# rs485.net
KiCad netlist of a schematic drawn in Altium Designer
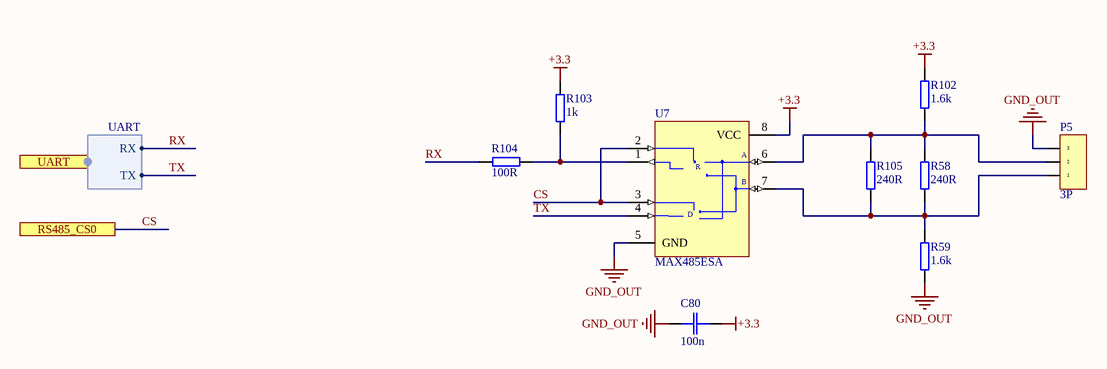
[diagram p0: rs485.SchDoc]

(export (version "E")
  (design (tool "Eeschema 10.0.6"))
  (components
    (comp (ref "C80") (value "100n") (footprint "CAP: 0603") (libsource (lib "PASSIVE") (part "C_SMD")))
    (comp (ref "P5") (value "3P") (footprint "CON: 3P V 3.5mm") (libsource (lib "CONNECTOR") (part "3P")))
    (comp (ref "R58") (value "240R") (footprint "RES: 0603") (libsource (lib "PASSIVE") (part "R_SMD")))
    (comp (ref "R59") (value "1.6k") (footprint "RES: 0603") (libsource (lib "PASSIVE") (part "R_SMD")))
    (comp (ref "R102") (value "1.6k") (footprint "RES: 0603") (libsource (lib "PASSIVE") (part "R_SMD")))
    (comp (ref "R103") (value "1k") (footprint "RES: 0603") (libsource (lib "PASSIVE") (part "R_SMD")))
    (comp (ref "R104") (value "100R") (footprint "RES: 0603") (libsource (lib "PASSIVE") (part "R_SMD")))
    (comp (ref "R105") (value "240R") (footprint "RES: 0603") (libsource (lib "PASSIVE") (part "R_SMD")))
    (comp (ref "U7")
      (value "MAX485ESA")
      (footprint "NSO8_N")
      (description "Low-Power, Slew-Rate-Limited RS-485/RS-422 Transceiver")
      (fields (field (name "PUBLISHER") "Altium Limited"))
      (libsource (lib "Maxim Communication Transceiver") (part "MAX485ESA"))
    )
  )
  (nets
    (net (code "2") (name "+3.3") (class "Default")
      (node (ref "C80") (pin "2") (pinfunction "2_2") (pintype "passive"))
      (node (ref "R102") (pin "1") (pinfunction "1_1") (pintype "passive"))
      (node (ref "R103") (pin "1") (pinfunction "1_1") (pintype "passive"))
      (node (ref "U7") (pin "8") (pinfunction "VCC_8") (pintype "power_in"))
    )
    (net (code "3") (name "/CS") (class "Default")
      (node (ref "U7") (pin "2") (pinfunction "~{RE}_2") (pintype "input"))
      (node (ref "U7") (pin "3") (pinfunction "DE_3") (pintype "input"))
    )
    (net (code "4") (name "/RX") (class "Default")
      (node (ref "R104") (pin "2") (pinfunction "2_2") (pintype "passive"))
    )
    (net (code "5") (name "/TX") (class "Default")
      (node (ref "U7") (pin "4") (pinfunction "DI_4") (pintype "input"))
    )
    (net (code "7") (name "GND_OUT") (class "Default")
      (node (ref "C80") (pin "1") (pinfunction "1_1") (pintype "passive"))
      (node (ref "P5") (pin "3") (pinfunction "3_3") (pintype "passive"))
      (node (ref "R59") (pin "2") (pinfunction "2_2") (pintype "passive"))
      (node (ref "U7") (pin "5") (pinfunction "GND_5") (pintype "power_in"))
    )
    (net (code "8") (name "Net-(U7-A)") (class "Default")
      (node (ref "P5") (pin "2") (pinfunction "2_2") (pintype "passive"))
      (node (ref "R102") (pin "2") (pinfunction "2_2") (pintype "passive"))
      (node (ref "R105") (pin "1") (pinfunction "1_1") (pintype "passive"))
      (node (ref "R58") (pin "1") (pinfunction "1_1") (pintype "passive"))
      (node (ref "U7") (pin "6") (pinfunction "A_6") (pintype "bidirectional"))
    )
    (net (code "9") (name "Net-(U7-B)") (class "Default")
      (node (ref "P5") (pin "1") (pinfunction "1_1") (pintype "passive"))
      (node (ref "R105") (pin "2") (pinfunction "2_2") (pintype "passive"))
      (node (ref "R58") (pin "2") (pinfunction "2_2") (pintype "passive"))
      (node (ref "R59") (pin "1") (pinfunction "1_1") (pintype "passive"))
      (node (ref "U7") (pin "7") (pinfunction "B_7") (pintype "bidirectional"))
    )
    (net (code "10") (name "Net-(U7-RO)") (class "Default")
      (node (ref "R103") (pin "2") (pinfunction "2_2") (pintype "passive"))
      (node (ref "R104") (pin "1") (pinfunction "1_1") (pintype "passive"))
      (node (ref "U7") (pin "1") (pinfunction "RO_1") (pintype "output"))
    )
  )
)
